# CropPred.net
KiCad netlist of a schematic drawn in Altium Designer
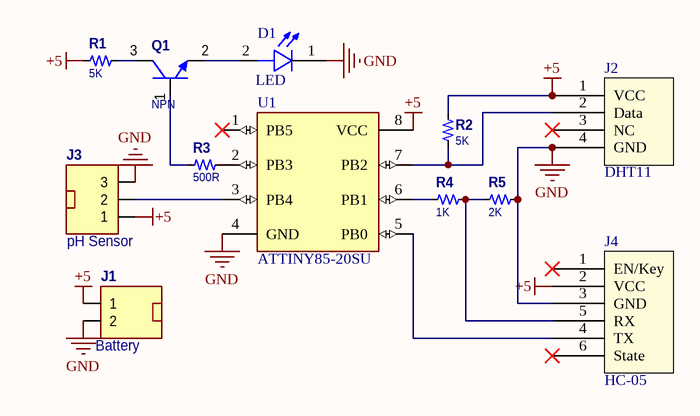
[diagram p0: CropPred.SchDoc]

(export (version "E")
  (design (tool "Eeschema 10.0.6"))
  (components
    (comp (ref "D1")
      (value "LED")
      (footprint "LED_APA3010QBC/G-GX")
      (description "Surface Mount LED; Size : 3.0X1.0mm ; Color: Blue; Lens: Water Clear")
      (fields (field (name "MP") "APA3010QBC/G-GX"))
      (libsource (lib "Indicator_Board") (part "APA3010QBC/G-GX"))
    )
    (comp (ref "J1")
      (value "Battery")
      (footprint "CON_HDR1x2_2p50_RA_SHRD_JST_S2B-HX-A")
      (description "Conn Shrouded Header HDR 2 POS 2.5mm Solder RA Thru-Hole Box")
      (fields
        (field (name "MANUFACTURER") "JST")
        (field (name "MANUFACTURER PART NUMBER") "S2B-XH-A(LF)(SN)")
      )
      (libsource (lib "Connectors") (part "CON_HDR1x2_2p50_RA_SHRD_JST_S2B-XH-A"))
    )
    (comp (ref "J2") (value "DHT11") (footprint "4posF") (libsource (lib "Crops_Predictor") (part "DHT11")))
    (comp (ref "J3")
      (value "pH Sensor")
      (footprint "CON_HDR1x3_2p50_RA_SHRD_JST-S3B-XH-A")
      (description "Conn Shrouded Header (4 Sides) HDR 3 POS 2.5mm Solder RA Side Entry Thru-Hole Box")
      (fields
        (field (name "MANUFACTURER") "JST")
        (field (name "MANUFACTURER PART NUMBER") "S3B-XH-A(LF)(SN)")
      )
      (libsource (lib "Connectors") (part "CON_HDR1x3_2p50_RA_SHRD_JST_S3B-XH-A"))
    )
    (comp (ref "J4") (value "HC-05") (footprint "6posf") (libsource (lib "Crops_Predictor") (part "HC05")))
    (comp (ref "Q1")
      (value "NPN")
      (footprint "SOT323")
      (description "Bipolar (BJT) Transistor NPN 40V 200mA 300MHz 200mW Surface Mount SOT-323")
      (fields
        (field (name "MANUFACTURER") "ON Semiconductor")
        (field (name "MANUFACTURER PART NUMBER") "BC817-40LT3G")
      )
      (libsource (lib "Transistors") (part "Q_NPN 40V 0.2A SOT323"))
    )
    (comp (ref "R1")
      (value "5K")
      (footprint "0603-R_N")
      (description "YAGEO - RC0603FR-070RL - RES, THICK FILM, 0R, 1%, 0.1W, 0603")
      (fields
        (field (name "MANUFACTURER") "Yageo")
        (field (name "MANUFACTURER PART NUMBER") "RC0603FR-070RL")
      )
      (libsource (lib "Resistors") (part "R_0R_1/10W_1%_0603"))
    )
    (comp (ref "R2")
      (value "5K")
      (footprint "0603-R_N")
      (description "YAGEO - RC0603FR-070RL - RES, THICK FILM, 0R, 1%, 0.1W, 0603")
      (fields
        (field (name "MANUFACTURER") "Yageo")
        (field (name "MANUFACTURER PART NUMBER") "RC0603FR-070RL")
      )
      (libsource (lib "Resistors") (part "R_0R_1/10W_1%_0603"))
    )
    (comp (ref "R3")
      (value "500R")
      (footprint "0603-R_N")
      (description "YAGEO - RC0603FR-070RL - RES, THICK FILM, 0R, 1%, 0.1W, 0603")
      (fields
        (field (name "MANUFACTURER") "Yageo")
        (field (name "MANUFACTURER PART NUMBER") "RC0603FR-070RL")
      )
      (libsource (lib "Resistors") (part "R_0R_1/10W_1%_0603"))
    )
    (comp (ref "R4")
      (value "1K")
      (footprint "0603-R_N")
      (description "YAGEO - RC0603FR-070RL - RES, THICK FILM, 0R, 1%, 0.1W, 0603")
      (fields
        (field (name "MANUFACTURER") "Yageo")
        (field (name "MANUFACTURER PART NUMBER") "RC0603FR-070RL")
      )
      (libsource (lib "Resistors") (part "R_0R_1/10W_1%_0603"))
    )
    (comp (ref "R5")
      (value "2K")
      (footprint "0603-R_N")
      (description "YAGEO - RC0603FR-070RL - RES, THICK FILM, 0R, 1%, 0.1W, 0603")
      (fields
        (field (name "MANUFACTURER") "Yageo")
        (field (name "MANUFACTURER PART NUMBER") "RC0603FR-070RL")
      )
      (libsource (lib "Resistors") (part "R_0R_1/10W_1%_0603"))
    )
    (comp (ref "U1")
      (value "ATTINY85-20SU")
      (footprint "SOIC127P798X216-8N")
      (fields (field (name "MF") "Microchip"))
      (libsource (lib "Crops_Predictor") (part "ATTINY85-20SU"))
    )
  )
  (nets
    (net (code "1") (name "+5") (class "Default")
      (node (ref "J1") (pin "1") (pinfunction "1_1") (pintype "passive"))
      (node (ref "J2") (pin "1") (pinfunction "VCC_1") (pintype "passive"))
      (node (ref "J3") (pin "1") (pinfunction "1_1") (pintype "passive"))
      (node (ref "J4") (pin "2") (pinfunction "VCC_2") (pintype "passive"))
      (node (ref "R1") (pin "2") (pinfunction "2_2") (pintype "passive"))
      (node (ref "R2") (pin "2") (pinfunction "2_2") (pintype "passive"))
      (node (ref "U1") (pin "8") (pinfunction "VCC_8") (pintype "power_in"))
    )
    (net (code "2") (name "GND") (class "Default")
      (node (ref "D1") (pin "1") (pinfunction "C_1") (pintype "passive"))
      (node (ref "J1") (pin "2") (pinfunction "2_2") (pintype "passive"))
      (node (ref "J2") (pin "4") (pinfunction "GND_4") (pintype "passive"))
      (node (ref "J3") (pin "3") (pinfunction "3_3") (pintype "passive"))
      (node (ref "J4") (pin "3") (pinfunction "GND_3") (pintype "passive"))
      (node (ref "R5") (pin "1") (pinfunction "1_1") (pintype "passive"))
      (node (ref "U1") (pin "4") (pinfunction "GND_4") (pintype "power_in"))
    )
    (net (code "3") (name "Net-(D1-A)") (class "Default")
      (node (ref "D1") (pin "2") (pinfunction "A_2") (pintype "passive"))
      (node (ref "Q1") (pin "2") (pinfunction "Emitter_2") (pintype "passive"))
    )
    (net (code "4") (name "Net-(J2-Data)") (class "Default")
      (node (ref "J2") (pin "2") (pinfunction "Data_2") (pintype "passive"))
      (node (ref "R2") (pin "1") (pinfunction "1_1") (pintype "passive"))
      (node (ref "U1") (pin "7") (pinfunction "PB2_7") (pintype "bidirectional"))
    )
    (net (code "5") (name "Net-(J4-RX)") (class "Default")
      (node (ref "J4") (pin "5") (pinfunction "RX_5") (pintype "passive"))
      (node (ref "R4") (pin "1") (pinfunction "1_1") (pintype "passive"))
      (node (ref "R5") (pin "2") (pinfunction "2_2") (pintype "passive"))
    )
    (net (code "6") (name "Net-(J4-TX)") (class "Default")
      (node (ref "J4") (pin "4") (pinfunction "TX_4") (pintype "passive"))
      (node (ref "U1") (pin "5") (pinfunction "PB0_5") (pintype "bidirectional"))
    )
    (net (code "7") (name "Net-(Q1-Base)") (class "Default")
      (node (ref "Q1") (pin "1") (pinfunction "Base_1") (pintype "passive"))
      (node (ref "R3") (pin "2") (pinfunction "2_2") (pintype "passive"))
    )
    (net (code "8") (name "Net-(Q1-Collector)") (class "Default")
      (node (ref "Q1") (pin "3") (pinfunction "Collector_3") (pintype "passive"))
      (node (ref "R1") (pin "1") (pinfunction "1_1") (pintype "passive"))
    )
    (net (code "9") (name "Net-(U1-PB1)") (class "Default")
      (node (ref "R4") (pin "2") (pinfunction "2_2") (pintype "passive"))
      (node (ref "U1") (pin "6") (pinfunction "PB1_6") (pintype "bidirectional"))
    )
    (net (code "10") (name "Net-(U1-PB3)") (class "Default")
      (node (ref "R3") (pin "1") (pinfunction "1_1") (pintype "passive"))
      (node (ref "U1") (pin "2") (pinfunction "PB3_2") (pintype "bidirectional"))
    )
    (net (code "11") (name "Net-(U1-PB4)") (class "Default")
      (node (ref "J3") (pin "2") (pinfunction "2_2") (pintype "passive"))
      (node (ref "U1") (pin "3") (pinfunction "PB4_3") (pintype "bidirectional"))
    )
    (net (code "12") (name "unconnected-(J2-NC-Pad3)") (class "Default")
      (node (ref "J2") (pin "3") (pinfunction "NC_3") (pintype "passive+no_connect"))
    )
    (net (code "13") (name "unconnected-(J4-EN{slash}Key-Pad1)") (class "Default")
      (node (ref "J4") (pin "1") (pinfunction "EN/Key_1") (pintype "passive+no_connect"))
    )
    (net (code "14") (name "unconnected-(J4-State-Pad6)") (class "Default")
      (node (ref "J4") (pin "6") (pinfunction "State_6") (pintype "passive+no_connect"))
    )
    (net (code "15") (name "unconnected-(U1-PB5-Pad1)") (class "Default")
      (node (ref "U1") (pin "1") (pinfunction "PB5_1") (pintype "bidirectional+no_connect"))
    )
  )
)
